# MainsFreqMon_RevA.net
KiCad netlist of a schematic drawn in EAGLE
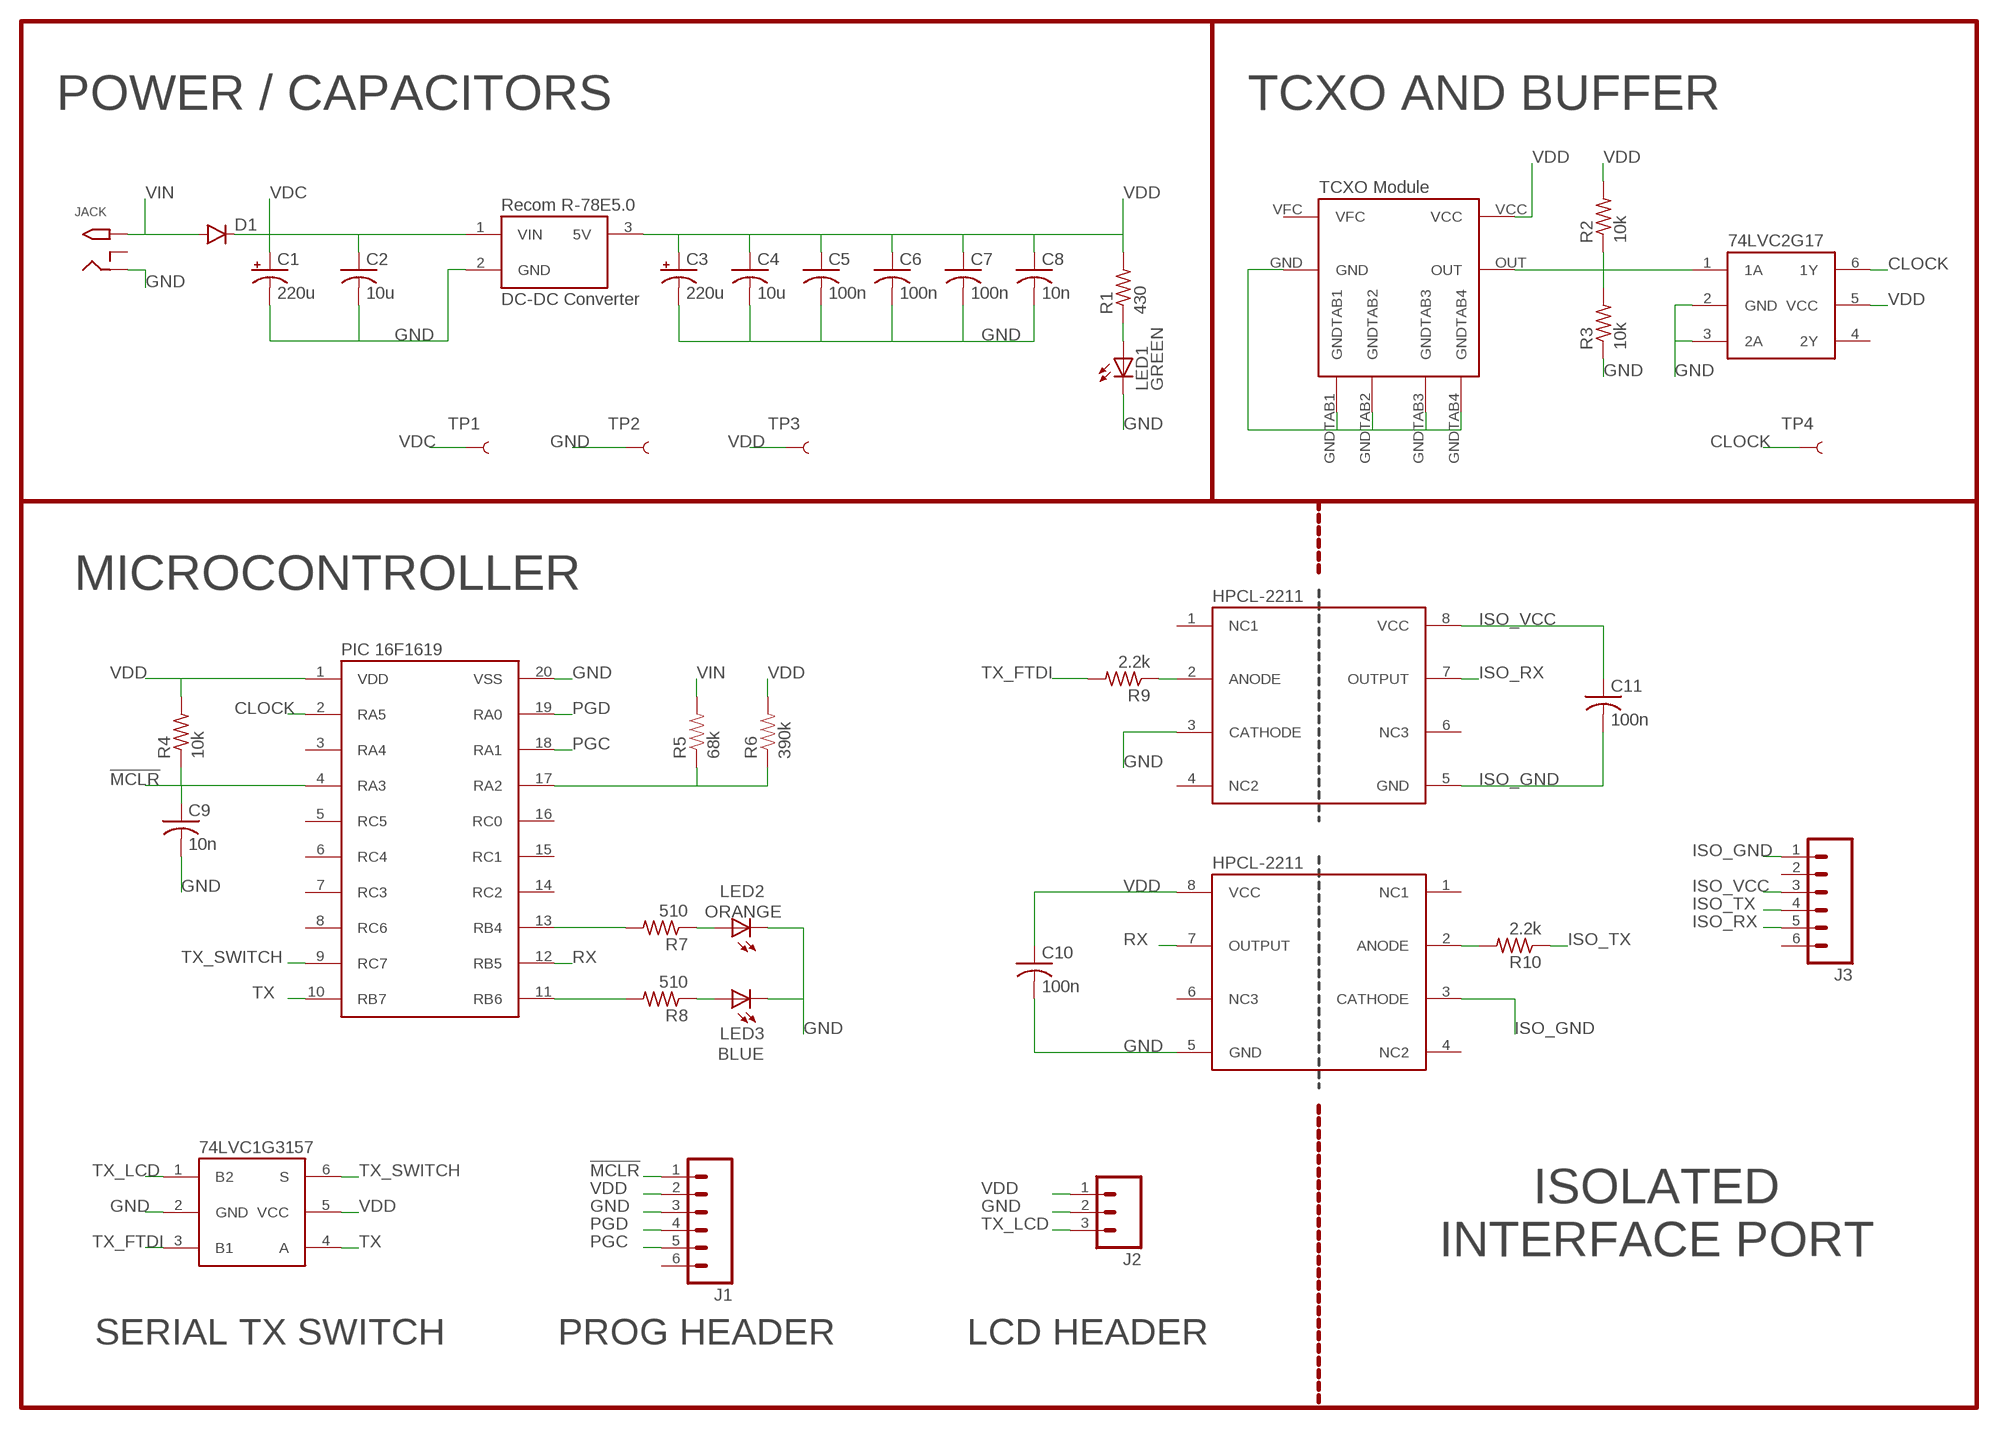
[diagram p0: schematic, sheet 1]

(export (version "E")
  (design (tool "Eeschema 10.0.6"))
  (components
    (comp (ref "C1")
      (value "220u")
      (footprint "eagle-import:E3,5-8")
      (libsource (lib "eagle-import") (part "CPOL-USE3.5-8"))
    )
    (comp (ref "C2")
      (value "10u")
      (footprint "eagle-import:C0805")
      (libsource (lib "eagle-import") (part "C-USC0805"))
    )
    (comp (ref "C3")
      (value "220u")
      (footprint "eagle-import:E3,5-8")
      (libsource (lib "eagle-import") (part "CPOL-USE3.5-8"))
    )
    (comp (ref "C4")
      (value "10u")
      (footprint "eagle-import:C0805")
      (libsource (lib "eagle-import") (part "C-USC0805"))
    )
    (comp (ref "C5")
      (value "100n")
      (footprint "eagle-import:C0805")
      (libsource (lib "eagle-import") (part "C-USC0805"))
    )
    (comp (ref "C6")
      (value "100n")
      (footprint "eagle-import:C0805")
      (libsource (lib "eagle-import") (part "C-USC0805"))
    )
    (comp (ref "C7")
      (value "100n")
      (footprint "eagle-import:C0805")
      (libsource (lib "eagle-import") (part "C-USC0805"))
    )
    (comp (ref "C8")
      (value "10n")
      (footprint "eagle-import:C0805")
      (libsource (lib "eagle-import") (part "C-USC0805"))
    )
    (comp (ref "C9")
      (value "10n")
      (footprint "eagle-import:C0805")
      (libsource (lib "eagle-import") (part "C-USC0805"))
    )
    (comp (ref "C10")
      (value "100n")
      (footprint "eagle-import:C0805")
      (libsource (lib "eagle-import") (part "C-USC0805"))
    )
    (comp (ref "C11")
      (value "100n")
      (footprint "eagle-import:C0805")
      (libsource (lib "eagle-import") (part "C-USC0805"))
    )
    (comp (ref "D1")
      (value "DIODEPTH")
      (footprint "eagle-import:DIODE-1N4001")
      (libsource (lib "eagle-import") (part "DIODEPTH"))
    )
    (comp (ref "J1")
      (value "M06SILK_FEMALE_PTH")
      (footprint "eagle-import:1X06")
      (libsource (lib "eagle-import") (part "SparkFun-ConnectorsNEW_M06SILK_FEMALE_PTH"))
    )
    (comp (ref "J2")
      (value "M03PTH")
      (footprint "eagle-import:1X03")
      (libsource (lib "eagle-import") (part "M03PTH"))
    )
    (comp (ref "J3")
      (value "M06SILK_FEMALE_PTH")
      (footprint "eagle-import:1X06")
      (libsource (lib "eagle-import") (part "M06SILK_FEMALE_PTH"))
    )
    (comp (ref "JACK")
      (value "2.1MMJACKTHM")
      (footprint "eagle-import:PJ-102A")
      (libsource (lib "eagle-import") (part "2.1MMJACKTHM"))
    )
    (comp (ref "LED1")
      (value "GREEN")
      (footprint "eagle-import:CHIPLED_1206")
      (libsource (lib "eagle-import") (part "LEDCHIPLED_1206"))
    )
    (comp (ref "LED2")
      (value "ORANGE")
      (footprint "eagle-import:CHIPLED_1206")
      (libsource (lib "eagle-import") (part "LEDCHIPLED_1206"))
    )
    (comp (ref "LED3")
      (value "BLUE")
      (footprint "eagle-import:CHIPLED_1206")
      (libsource (lib "eagle-import") (part "LEDCHIPLED_1206"))
    )
    (comp (ref "R1")
      (value "430")
      (footprint "eagle-import:R0805")
      (libsource (lib "eagle-import") (part "R-US_R0805"))
    )
    (comp (ref "R2")
      (value "10k")
      (footprint "eagle-import:R0805")
      (libsource (lib "eagle-import") (part "R-US_R0805"))
    )
    (comp (ref "R3")
      (value "10k")
      (footprint "eagle-import:R0805")
      (libsource (lib "eagle-import") (part "R-US_R0805"))
    )
    (comp (ref "R4")
      (value "10k")
      (footprint "eagle-import:R0805")
      (libsource (lib "eagle-import") (part "R-US_R0805"))
    )
    (comp (ref "R5")
      (value "68k")
      (footprint "eagle-import:AXIAL-0.4")
      (libsource (lib "eagle-import") (part "RESISTORPTH-1/4W"))
    )
    (comp (ref "R6")
      (value "390k")
      (footprint "eagle-import:AXIAL-0.4")
      (libsource (lib "eagle-import") (part "RESISTORPTH-1/4W"))
    )
    (comp (ref "R7")
      (value "510")
      (footprint "eagle-import:R0805")
      (libsource (lib "eagle-import") (part "R-US_R0805"))
    )
    (comp (ref "R8")
      (value "510")
      (footprint "eagle-import:R0805")
      (libsource (lib "eagle-import") (part "R-US_R0805"))
    )
    (comp (ref "R9")
      (value "2.2k")
      (footprint "eagle-import:R0805")
      (libsource (lib "eagle-import") (part "R-US_R0805"))
    )
    (comp (ref "R10")
      (value "2.2k")
      (footprint "eagle-import:R0805")
      (libsource (lib "eagle-import") (part "R-US_R0805"))
    )
    (comp (ref "RG1")
      (value "R-78C5.0")
      (footprint "eagle-import:R-78C5.0")
      (libsource (lib "eagle-import") (part "R-78C5.0"))
    )
    (comp (ref "TP1")
      (value "TEST-POINT3X5")
      (footprint "eagle-import:PAD.03X.05")
      (libsource (lib "eagle-import") (part "TEST-POINT3X5"))
    )
    (comp (ref "TP2")
      (value "TEST-POINT3X5")
      (footprint "eagle-import:PAD.03X.05")
      (libsource (lib "eagle-import") (part "TEST-POINT3X5"))
    )
    (comp (ref "TP3")
      (value "TEST-POINT3X5")
      (footprint "eagle-import:PAD.03X.05")
      (libsource (lib "eagle-import") (part "TEST-POINT3X5"))
    )
    (comp (ref "TP4")
      (value "TEST-POINT3X5")
      (footprint "eagle-import:PAD.03X.05")
      (libsource (lib "eagle-import") (part "TEST-POINT3X5"))
    )
    (comp (ref "U1")
      (value "16F1619")
      (footprint "eagle-import:SO20L")
      (libsource (lib "eagle-import") (part "16F1619"))
    )
    (comp (ref "U2")
      (value "74LVC2G14/7")
      (footprint "eagle-import:SOT23-6")
      (libsource (lib "eagle-import") (part "74LVC2G14/7"))
    )
    (comp (ref "U3")
      (value "74LVC1G3157")
      (footprint "eagle-import:SOT23-6")
      (libsource (lib "eagle-import") (part "74LVC1G3157"))
    )
    (comp (ref "U4")
      (value "HPCL2211")
      (footprint "eagle-import:DIP08")
      (libsource (lib "eagle-import") (part "HPCL2211"))
    )
    (comp (ref "U5")
      (value "HPCL2211")
      (footprint "eagle-import:DIP08")
      (libsource (lib "eagle-import") (part "HPCL2211"))
    )
    (comp (ref "X1")
      (value "TCXO2")
      (footprint "eagle-import:TCXO2")
      (libsource (lib "eagle-import") (part "TCXO2"))
    )
  )
  (nets
    (net (code "1") (name "/CLOCK") (class "Default")
      (node (ref "TP4") (pin "P$1") (pinfunction "1_P$1") (pintype "bidirectional"))
      (node (ref "U1") (pin "2") (pinfunction "RA5_2") (pintype "bidirectional"))
      (node (ref "U2") (pin "6") (pinfunction "1Y_6") (pintype "bidirectional"))
    )
    (net (code "2") (name "/GND") (class "Default")
      (node (ref "C1") (pin "-") (pinfunction "-_-") (pintype "passive"))
      (node (ref "C10") (pin "2") (pinfunction "2_2") (pintype "passive"))
      (node (ref "C2") (pin "2") (pinfunction "2_2") (pintype "passive"))
      (node (ref "C3") (pin "-") (pinfunction "-_-") (pintype "passive"))
      (node (ref "C4") (pin "2") (pinfunction "2_2") (pintype "passive"))
      (node (ref "C5") (pin "2") (pinfunction "2_2") (pintype "passive"))
      (node (ref "C6") (pin "2") (pinfunction "2_2") (pintype "passive"))
      (node (ref "C7") (pin "2") (pinfunction "2_2") (pintype "passive"))
      (node (ref "C8") (pin "2") (pinfunction "2_2") (pintype "passive"))
      (node (ref "C9") (pin "2") (pinfunction "2_2") (pintype "passive"))
      (node (ref "J1") (pin "3") (pinfunction "3_3") (pintype "passive"))
      (node (ref "J2") (pin "2") (pinfunction "2_2") (pintype "passive"))
      (node (ref "JACK") (pin "RING") (pinfunction "RING_RING") (pintype "bidirectional"))
      (node (ref "LED1") (pin "C") (pinfunction "C_C") (pintype "passive"))
      (node (ref "LED2") (pin "C") (pinfunction "C_C") (pintype "passive"))
      (node (ref "LED3") (pin "C") (pinfunction "C_C") (pintype "passive"))
      (node (ref "R3") (pin "1") (pinfunction "1_1") (pintype "passive"))
      (node (ref "RG1") (pin "2") (pinfunction "GND_2") (pintype "bidirectional"))
      (node (ref "TP2") (pin "P$1") (pinfunction "1_P$1") (pintype "bidirectional"))
      (node (ref "U1") (pin "20") (pinfunction "VSS_20") (pintype "bidirectional"))
      (node (ref "U2") (pin "2") (pinfunction "GND_2") (pintype "bidirectional"))
      (node (ref "U2") (pin "3") (pinfunction "2A_3") (pintype "bidirectional"))
      (node (ref "U3") (pin "2") (pinfunction "GND_2") (pintype "bidirectional"))
      (node (ref "U4") (pin "3") (pinfunction "CATHODE_3") (pintype "bidirectional"))
      (node (ref "U5") (pin "5") (pinfunction "GND_5") (pintype "bidirectional"))
      (node (ref "X1") (pin "GND") (pinfunction "GND_GND") (pintype "bidirectional"))
      (node (ref "X1") (pin "GNDTAB1") (pinfunction "GNDTAB1_GNDTAB1") (pintype "bidirectional"))
      (node (ref "X1") (pin "GNDTAB2") (pinfunction "GNDTAB2_GNDTAB2") (pintype "bidirectional"))
      (node (ref "X1") (pin "GNDTAB3") (pinfunction "GNDTAB3_GNDTAB3") (pintype "bidirectional"))
      (node (ref "X1") (pin "GNDTAB4") (pinfunction "GNDTAB4_GNDTAB4") (pintype "bidirectional"))
    )
    (net (code "3") (name "/ISO_GND") (class "Default")
      (node (ref "C11") (pin "2") (pinfunction "2_2") (pintype "passive"))
      (node (ref "J3") (pin "1") (pinfunction "1_1") (pintype "passive"))
      (node (ref "U4") (pin "5") (pinfunction "GND_5") (pintype "bidirectional"))
      (node (ref "U5") (pin "3") (pinfunction "CATHODE_3") (pintype "bidirectional"))
    )
    (net (code "4") (name "/ISO_RX") (class "Default")
      (node (ref "J3") (pin "5") (pinfunction "5_5") (pintype "passive"))
      (node (ref "U4") (pin "7") (pinfunction "OUTPUT_7") (pintype "bidirectional"))
    )
    (net (code "5") (name "/ISO_TX") (class "Default")
      (node (ref "J3") (pin "4") (pinfunction "4_4") (pintype "passive"))
      (node (ref "R10") (pin "1") (pinfunction "1_1") (pintype "passive"))
    )
    (net (code "6") (name "/ISO_VCC") (class "Default")
      (node (ref "C11") (pin "1") (pinfunction "1_1") (pintype "passive"))
      (node (ref "J3") (pin "3") (pinfunction "3_3") (pintype "passive"))
      (node (ref "U4") (pin "8") (pinfunction "VCC_8") (pintype "bidirectional"))
    )
    (net (code "7") (name "/PGC") (class "Default")
      (node (ref "J1") (pin "5") (pinfunction "5_5") (pintype "passive"))
      (node (ref "U1") (pin "18") (pinfunction "RA1_18") (pintype "bidirectional"))
    )
    (net (code "8") (name "/PGD") (class "Default")
      (node (ref "J1") (pin "4") (pinfunction "4_4") (pintype "passive"))
      (node (ref "U1") (pin "19") (pinfunction "RA0_19") (pintype "bidirectional"))
    )
    (net (code "9") (name "/RX") (class "Default")
      (node (ref "U1") (pin "12") (pinfunction "RB5_12") (pintype "bidirectional"))
      (node (ref "U5") (pin "7") (pinfunction "OUTPUT_7") (pintype "bidirectional"))
    )
    (net (code "10") (name "/TX") (class "Default")
      (node (ref "U1") (pin "10") (pinfunction "RB7_10") (pintype "bidirectional"))
      (node (ref "U3") (pin "4") (pinfunction "A_4") (pintype "bidirectional"))
    )
    (net (code "11") (name "/TX_FTDI") (class "Default")
      (node (ref "R9") (pin "2") (pinfunction "2_2") (pintype "passive"))
      (node (ref "U3") (pin "3") (pinfunction "B1_3") (pintype "bidirectional"))
    )
    (net (code "12") (name "/TX_LCD") (class "Default")
      (node (ref "J2") (pin "3") (pinfunction "3_3") (pintype "passive"))
      (node (ref "U3") (pin "1") (pinfunction "B2_1") (pintype "bidirectional"))
    )
    (net (code "13") (name "/TX_SWITCH") (class "Default")
      (node (ref "U1") (pin "9") (pinfunction "RC7_9") (pintype "bidirectional"))
      (node (ref "U3") (pin "6") (pinfunction "S_6") (pintype "bidirectional"))
    )
    (net (code "14") (name "/VDC") (class "Default")
      (node (ref "C1") (pin "+") (pinfunction "+_+") (pintype "passive"))
      (node (ref "C2") (pin "1") (pinfunction "1_1") (pintype "passive"))
      (node (ref "D1") (pin "C") (pinfunction "C_C") (pintype "passive"))
      (node (ref "RG1") (pin "1") (pinfunction "VIN_1") (pintype "bidirectional"))
      (node (ref "TP1") (pin "P$1") (pinfunction "1_P$1") (pintype "bidirectional"))
    )
    (net (code "15") (name "/VDD") (class "Default")
      (node (ref "C10") (pin "1") (pinfunction "1_1") (pintype "passive"))
      (node (ref "C3") (pin "+") (pinfunction "+_+") (pintype "passive"))
      (node (ref "C4") (pin "1") (pinfunction "1_1") (pintype "passive"))
      (node (ref "C5") (pin "1") (pinfunction "1_1") (pintype "passive"))
      (node (ref "C6") (pin "1") (pinfunction "1_1") (pintype "passive"))
      (node (ref "C7") (pin "1") (pinfunction "1_1") (pintype "passive"))
      (node (ref "C8") (pin "1") (pinfunction "1_1") (pintype "passive"))
      (node (ref "J1") (pin "2") (pinfunction "2_2") (pintype "passive"))
      (node (ref "J2") (pin "1") (pinfunction "1_1") (pintype "passive"))
      (node (ref "R1") (pin "2") (pinfunction "2_2") (pintype "passive"))
      (node (ref "R2") (pin "2") (pinfunction "2_2") (pintype "passive"))
      (node (ref "R4") (pin "2") (pinfunction "2_2") (pintype "passive"))
      (node (ref "R6") (pin "P$2") (pinfunction "2_P$2") (pintype "passive"))
      (node (ref "RG1") (pin "3") (pinfunction "5V_3") (pintype "bidirectional"))
      (node (ref "TP3") (pin "P$1") (pinfunction "1_P$1") (pintype "bidirectional"))
      (node (ref "U1") (pin "1") (pinfunction "VDD_1") (pintype "bidirectional"))
      (node (ref "U2") (pin "5") (pinfunction "VCC_5") (pintype "bidirectional"))
      (node (ref "U3") (pin "5") (pinfunction "VCC_5") (pintype "bidirectional"))
      (node (ref "U5") (pin "8") (pinfunction "VCC_8") (pintype "bidirectional"))
      (node (ref "X1") (pin "VCC") (pinfunction "VCC_VCC") (pintype "bidirectional"))
    )
    (net (code "16") (name "/VIN") (class "Default")
      (node (ref "D1") (pin "A") (pinfunction "A_A") (pintype "passive"))
      (node (ref "JACK") (pin "TIP") (pinfunction "TIP_TIP") (pintype "bidirectional"))
      (node (ref "R5") (pin "P$2") (pinfunction "2_P$2") (pintype "passive"))
    )
    (net (code "17") (name "/~{MCLR}") (class "Default")
      (node (ref "C9") (pin "1") (pinfunction "1_1") (pintype "passive"))
      (node (ref "J1") (pin "1") (pinfunction "1_1") (pintype "passive"))
      (node (ref "R4") (pin "1") (pinfunction "1_1") (pintype "passive"))
      (node (ref "U1") (pin "4") (pinfunction "RA3_4") (pintype "bidirectional"))
    )
    (net (code "18") (name "Net-(LED1-PadA)") (class "Default")
      (node (ref "LED1") (pin "A") (pinfunction "A_A") (pintype "passive"))
      (node (ref "R1") (pin "1") (pinfunction "1_1") (pintype "passive"))
    )
    (net (code "19") (name "Net-(LED2-PadA)") (class "Default")
      (node (ref "LED2") (pin "A") (pinfunction "A_A") (pintype "passive"))
      (node (ref "R7") (pin "1") (pinfunction "1_1") (pintype "passive"))
    )
    (net (code "20") (name "Net-(LED3-PadA)") (class "Default")
      (node (ref "LED3") (pin "A") (pinfunction "A_A") (pintype "passive"))
      (node (ref "R8") (pin "1") (pinfunction "1_1") (pintype "passive"))
    )
    (net (code "21") (name "Net-(R5-1)") (class "Default")
      (node (ref "R5") (pin "P$1") (pinfunction "1_P$1") (pintype "passive"))
      (node (ref "R6") (pin "P$1") (pinfunction "1_P$1") (pintype "passive"))
      (node (ref "U1") (pin "17") (pinfunction "RA2_17") (pintype "bidirectional"))
    )
    (net (code "22") (name "Net-(U1-RB4)") (class "Default")
      (node (ref "R7") (pin "2") (pinfunction "2_2") (pintype "passive"))
      (node (ref "U1") (pin "13") (pinfunction "RB4_13") (pintype "bidirectional"))
    )
    (net (code "23") (name "Net-(U1-RB6)") (class "Default")
      (node (ref "R8") (pin "2") (pinfunction "2_2") (pintype "passive"))
      (node (ref "U1") (pin "11") (pinfunction "RB6_11") (pintype "bidirectional"))
    )
    (net (code "24") (name "Net-(U2-1A)") (class "Default")
      (node (ref "R2") (pin "1") (pinfunction "1_1") (pintype "passive"))
      (node (ref "R3") (pin "2") (pinfunction "2_2") (pintype "passive"))
      (node (ref "U2") (pin "1") (pinfunction "1A_1") (pintype "bidirectional"))
      (node (ref "X1") (pin "OUT") (pinfunction "OUT_OUT") (pintype "bidirectional"))
    )
    (net (code "25") (name "Net-(U4-ANODE)") (class "Default")
      (node (ref "R9") (pin "1") (pinfunction "1_1") (pintype "passive"))
      (node (ref "U4") (pin "2") (pinfunction "ANODE_2") (pintype "bidirectional"))
    )
    (net (code "26") (name "Net-(U5-ANODE)") (class "Default")
      (node (ref "R10") (pin "2") (pinfunction "2_2") (pintype "passive"))
      (node (ref "U5") (pin "2") (pinfunction "ANODE_2") (pintype "bidirectional"))
    )
    (net (code "27") (name "unconnected-(J1-Pad6)") (class "Default")
      (node (ref "J1") (pin "6") (pinfunction "6_6") (pintype "passive"))
    )
    (net (code "28") (name "unconnected-(J3-Pad2)") (class "Default")
      (node (ref "J3") (pin "2") (pinfunction "2_2") (pintype "passive"))
    )
    (net (code "29") (name "unconnected-(J3-Pad6)") (class "Default")
      (node (ref "J3") (pin "6") (pinfunction "6_6") (pintype "passive"))
    )
    (net (code "30") (name "unconnected-(JACK-PadRING_SW)") (class "Default")
      (node (ref "JACK") (pin "RING_SW") (pinfunction "RING_SW_RING_SW") (pintype "bidirectional"))
    )
    (net (code "31") (name "unconnected-(U1-RA4-Pad3)") (class "Default")
      (node (ref "U1") (pin "3") (pinfunction "RA4_3") (pintype "bidirectional"))
    )
    (net (code "32") (name "unconnected-(U1-RC0-Pad16)") (class "Default")
      (node (ref "U1") (pin "16") (pinfunction "RC0_16") (pintype "bidirectional"))
    )
    (net (code "33") (name "unconnected-(U1-RC1-Pad15)") (class "Default")
      (node (ref "U1") (pin "15") (pinfunction "RC1_15") (pintype "bidirectional"))
    )
    (net (code "34") (name "unconnected-(U1-RC2-Pad14)") (class "Default")
      (node (ref "U1") (pin "14") (pinfunction "RC2_14") (pintype "bidirectional"))
    )
    (net (code "35") (name "unconnected-(U1-RC3-Pad7)") (class "Default")
      (node (ref "U1") (pin "7") (pinfunction "RC3_7") (pintype "bidirectional"))
    )
    (net (code "36") (name "unconnected-(U1-RC4-Pad6)") (class "Default")
      (node (ref "U1") (pin "6") (pinfunction "RC4_6") (pintype "bidirectional"))
    )
    (net (code "37") (name "unconnected-(U1-RC5-Pad5)") (class "Default")
      (node (ref "U1") (pin "5") (pinfunction "RC5_5") (pintype "bidirectional"))
    )
    (net (code "38") (name "unconnected-(U1-RC6-Pad8)") (class "Default")
      (node (ref "U1") (pin "8") (pinfunction "RC6_8") (pintype "bidirectional"))
    )
    (net (code "39") (name "unconnected-(U2-2Y-Pad4)") (class "Default")
      (node (ref "U2") (pin "4") (pinfunction "2Y_4") (pintype "bidirectional"))
    )
    (net (code "40") (name "unconnected-(U4-NC1-Pad1)") (class "Default")
      (node (ref "U4") (pin "1") (pinfunction "NC1_1") (pintype "bidirectional"))
    )
    (net (code "41") (name "unconnected-(U4-NC2-Pad4)") (class "Default")
      (node (ref "U4") (pin "4") (pinfunction "NC2_4") (pintype "bidirectional"))
    )
    (net (code "42") (name "unconnected-(U4-NC3-Pad6)") (class "Default")
      (node (ref "U4") (pin "6") (pinfunction "NC3_6") (pintype "bidirectional"))
    )
    (net (code "43") (name "unconnected-(U5-NC1-Pad1)") (class "Default")
      (node (ref "U5") (pin "1") (pinfunction "NC1_1") (pintype "bidirectional"))
    )
    (net (code "44") (name "unconnected-(U5-NC2-Pad4)") (class "Default")
      (node (ref "U5") (pin "4") (pinfunction "NC2_4") (pintype "bidirectional"))
    )
    (net (code "45") (name "unconnected-(U5-NC3-Pad6)") (class "Default")
      (node (ref "U5") (pin "6") (pinfunction "NC3_6") (pintype "bidirectional"))
    )
    (net (code "46") (name "unconnected-(X1-PadVFC)") (class "Default")
      (node (ref "X1") (pin "VFC") (pinfunction "VFC_VFC") (pintype "bidirectional"))
    )
  )
)
